# 5V0_12V0_rails.net
KiCad netlist of a schematic drawn in Altium Designer
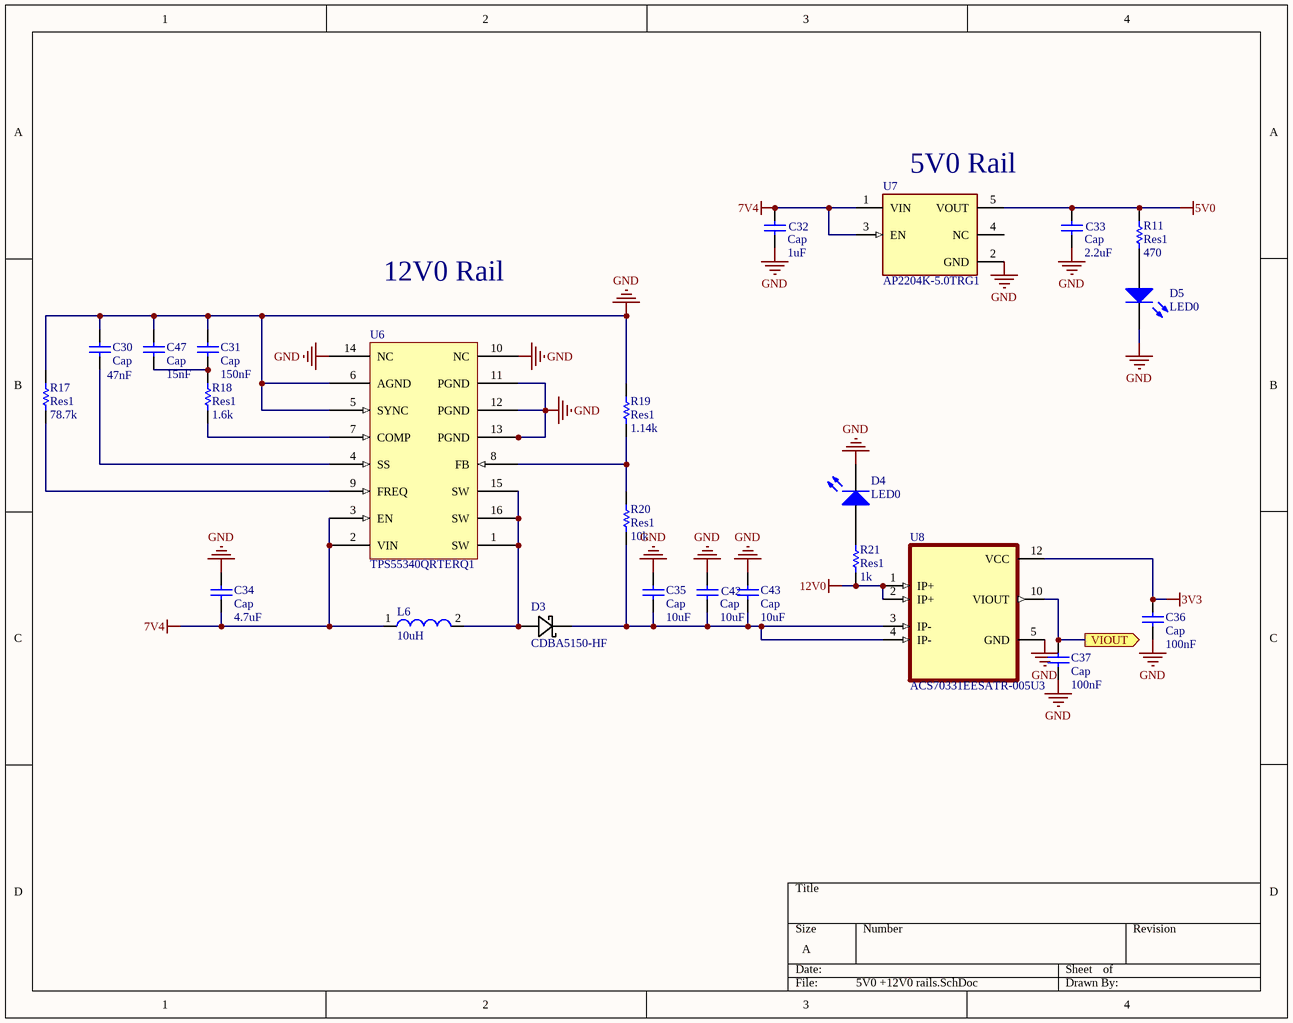
[diagram p0: 5V0 +12V0 rails.SchDoc]

(export (version "E")
  (design (tool "Eeschema 10.0.6"))
  (components
    (comp (ref "C30")
      (value "Cap")
      (footprint "0402-A")
      (description "Capacitor")
      (fields (field (name "ALTIUM_VALUE") "47nF") (field (name "PUBLISHER") "Altium Limited"))
      (libsource (lib "Miscellaneous Devices") (part "Cap"))
    )
    (comp (ref "C31")
      (value "Cap")
      (footprint "0402-A")
      (description "Capacitor")
      (fields (field (name "ALTIUM_VALUE") "150nF") (field (name "PUBLISHER") "Altium Limited"))
      (libsource (lib "Miscellaneous Devices") (part "Cap"))
    )
    (comp (ref "C32")
      (value "Cap")
      (footprint "1608[0603]")
      (description "Capacitor")
      (fields (field (name "ALTIUM_VALUE") "1uF") (field (name "PUBLISHER") "Altium Limited"))
      (libsource (lib "Miscellaneous Devices") (part "Cap"))
    )
    (comp (ref "C33")
      (value "Cap")
      (footprint "0402-A")
      (description "Capacitor")
      (fields (field (name "ALTIUM_VALUE") "2.2uF") (field (name "PUBLISHER") "Altium Limited"))
      (libsource (lib "Miscellaneous Devices") (part "Cap"))
    )
    (comp (ref "C34")
      (value "Cap")
      (footprint "6-0805_M")
      (description "Capacitor")
      (fields (field (name "ALTIUM_VALUE") "4.7uF") (field (name "PUBLISHER") "Altium Limited"))
      (libsource (lib "Miscellaneous Devices") (part "Cap"))
    )
    (comp (ref "C35")
      (value "Cap")
      (footprint "6-0805_M")
      (description "Capacitor")
      (fields (field (name "ALTIUM_VALUE") "10uF") (field (name "PUBLISHER") "Altium Limited"))
      (libsource (lib "Miscellaneous Devices") (part "Cap"))
    )
    (comp (ref "C36")
      (value "Cap")
      (footprint "1608[0603]")
      (description "Capacitor")
      (fields (field (name "ALTIUM_VALUE") "100nF") (field (name "PUBLISHER") "Altium Limited"))
      (libsource (lib "Miscellaneous Devices") (part "Cap"))
    )
    (comp (ref "C37")
      (value "Cap")
      (footprint "1608[0603]")
      (description "Capacitor")
      (fields (field (name "ALTIUM_VALUE") "100nF") (field (name "PUBLISHER") "Altium Limited"))
      (libsource (lib "Miscellaneous Devices") (part "Cap"))
    )
    (comp (ref "C42")
      (value "Cap")
      (footprint "6-0805_M")
      (description "Capacitor")
      (fields (field (name "ALTIUM_VALUE") "10uF") (field (name "PUBLISHER") "Altium Limited"))
      (libsource (lib "Miscellaneous Devices") (part "Cap"))
    )
    (comp (ref "C43")
      (value "Cap")
      (footprint "6-0805_M")
      (description "Capacitor")
      (fields (field (name "ALTIUM_VALUE") "10uF") (field (name "PUBLISHER") "Altium Limited"))
      (libsource (lib "Miscellaneous Devices") (part "Cap"))
    )
    (comp (ref "C47")
      (value "Cap")
      (footprint "0402-A")
      (description "Capacitor")
      (fields (field (name "ALTIUM_VALUE") "15nF") (field (name "PUBLISHER") "Altium Limited"))
      (libsource (lib "Miscellaneous Devices") (part "Cap"))
    )
    (comp (ref "D3")
      (value "CDBA5150-HF")
      (footprint "CDBA5")
      (description "No Description Available")
      (fields (field (name "COPYRIGHT") "Copyright (C) 2018 Accelerated Designs. All rights reserved"))
      (libsource (lib "schottlky diode 5A") (part "CDBA5150-HF"))
    )
    (comp (ref "D4")
      (value "LED0")
      (footprint "1608[0603]")
      (fields (field (name "PUBLISHER") "Altium Limited"))
      (libsource (lib "Miscellaneous Devices") (part "LED0"))
    )
    (comp (ref "D5")
      (value "LED0")
      (footprint "1608[0603]")
      (fields (field (name "PUBLISHER") "Altium Limited"))
      (libsource (lib "Miscellaneous Devices") (part "LED0"))
    )
    (comp (ref "L6")
      (value "10uH")
      (footprint "WE-PD-L")
      (description "SMD-Shielded Power Inductor WE-PD, L = 10.0 µH")
      (libsource (lib "Altium Content Vault") (part "PAS-IND-INDUCTOR-2"))
    )
    (comp (ref "R11")
      (value "Res1")
      (footprint "6-0805_M")
      (description "Resistor")
      (fields (field (name "ALTIUM_VALUE") "470") (field (name "PUBLISHER") "Altium Limited"))
      (libsource (lib "Miscellaneous Devices") (part "Res1"))
    )
    (comp (ref "R17")
      (value "Res1")
      (footprint "0402-A")
      (description "Resistor")
      (fields (field (name "ALTIUM_VALUE") "78.7k") (field (name "PUBLISHER") "Altium Limited"))
      (libsource (lib "Miscellaneous Devices") (part "Res1"))
    )
    (comp (ref "R18")
      (value "Res1")
      (footprint "0402-A")
      (description "Resistor")
      (fields (field (name "ALTIUM_VALUE") "1.6k") (field (name "PUBLISHER") "Altium Limited"))
      (libsource (lib "Miscellaneous Devices") (part "Res1"))
    )
    (comp (ref "R19")
      (value "Res1")
      (footprint "6-0805_M")
      (description "Resistor")
      (fields (field (name "ALTIUM_VALUE") "1.14k") (field (name "PUBLISHER") "Altium Limited"))
      (libsource (lib "Miscellaneous Devices") (part "Res1"))
    )
    (comp (ref "R20")
      (value "Res1")
      (footprint "0402-A")
      (description "Resistor")
      (fields (field (name "ALTIUM_VALUE") "10k") (field (name "PUBLISHER") "Altium Limited"))
      (libsource (lib "Miscellaneous Devices") (part "Res1"))
    )
    (comp (ref "R21")
      (value "Res1")
      (footprint "0402-A")
      (description "Resistor")
      (fields (field (name "ALTIUM_VALUE") "1k") (field (name "PUBLISHER") "Altium Limited"))
      (libsource (lib "Miscellaneous Devices") (part "Res1"))
    )
    (comp (ref "U6")
      (value "TPS55340QRTERQ1")
      (footprint "TPS55340QRTERQ1")
      (libsource (lib "TPS55340QRTERQ1") (part "TPS55340QRTERQ1"))
    )
    (comp (ref "U7")
      (value "AP2204K-5.0TRG1")
      (footprint "FP-SOT25-IPC_B")
      (description "IC REG LINEAR 5V 150MA SOT23-5")
      (libsource (lib "Altium Content Vault") (part "4edbc9a0bcf12f8a3abc99958da3ec2"))
    )
    (comp (ref "U8")
      (value "ACS70331EESATR-005U3")
      (footprint "ALLEGRO_ACS70331EESATR-005U3")
      (description "Current Sensor 5A 1 Channel Hall Effect, Open Loop Unidirectional 12-PowerWQFN")
      (fields
        (field (name "DIGI-KEY_PART_NUMBER") "620-1888-1-ND")
        (field (name "MF") "Allegro MicroSystems LLC")
      )
      (libsource (lib "ACS70331EESATR-005U3") (part "ACS70331EESATR-005U3"))
    )
  )
  (nets
    (net (code "1") (name "/VIOUT") (class "Default")
      (node (ref "C37") (pin "1") (pinfunction "1_1") (pintype "passive"))
      (node (ref "U8") (pin "10") (pinfunction "VIOUT_10") (pintype "output"))
    )
    (net (code "2") (name "3V3") (class "Default")
      (node (ref "C36") (pin "1") (pinfunction "1_1") (pintype "passive"))
      (node (ref "U8") (pin "12") (pinfunction "VCC_12") (pintype "power_in"))
    )
    (net (code "3") (name "5V0") (class "Default")
      (node (ref "C33") (pin "2") (pinfunction "2_2") (pintype "passive"))
      (node (ref "R11") (pin "2") (pinfunction "2_2") (pintype "passive"))
      (node (ref "U7") (pin "5") (pinfunction "VOUT_5") (pintype "power_in"))
    )
    (net (code "4") (name "7V4") (class "Default")
      (node (ref "C32") (pin "2") (pinfunction "2_2") (pintype "passive"))
      (node (ref "C34") (pin "1") (pinfunction "1_1") (pintype "passive"))
      (node (ref "L6") (pin "1") (pinfunction "1_1") (pintype "passive"))
      (node (ref "U6") (pin "2") (pinfunction "VIN_2") (pintype "power_in"))
      (node (ref "U6") (pin "3") (pinfunction "EN_3") (pintype "input"))
      (node (ref "U7") (pin "1") (pinfunction "VIN_1") (pintype "power_in"))
      (node (ref "U7") (pin "3") (pinfunction "EN_3") (pintype "input"))
    )
    (net (code "5") (name "12V0") (class "Default")
      (node (ref "R21") (pin "2") (pinfunction "2_2") (pintype "passive"))
      (node (ref "U8") (pin "1") (pinfunction "IP+_1") (pintype "input"))
      (node (ref "U8") (pin "2") (pinfunction "IP+_2") (pintype "input"))
    )
    (net (code "6") (name "GND") (class "Default")
      (node (ref "C30") (pin "2") (pinfunction "2_2") (pintype "passive"))
      (node (ref "C31") (pin "2") (pinfunction "2_2") (pintype "passive"))
      (node (ref "C32") (pin "1") (pinfunction "1_1") (pintype "passive"))
      (node (ref "C33") (pin "1") (pinfunction "1_1") (pintype "passive"))
      (node (ref "C34") (pin "2") (pinfunction "2_2") (pintype "passive"))
      (node (ref "C35") (pin "2") (pinfunction "2_2") (pintype "passive"))
      (node (ref "C36") (pin "2") (pinfunction "2_2") (pintype "passive"))
      (node (ref "C37") (pin "2") (pinfunction "2_2") (pintype "passive"))
      (node (ref "C42") (pin "2") (pinfunction "2_2") (pintype "passive"))
      (node (ref "C43") (pin "2") (pinfunction "2_2") (pintype "passive"))
      (node (ref "C47") (pin "2") (pinfunction "2_2") (pintype "passive"))
      (node (ref "D4") (pin "2") (pinfunction "K_2") (pintype "passive"))
      (node (ref "D5") (pin "2") (pinfunction "K_2") (pintype "passive"))
      (node (ref "R17") (pin "2") (pinfunction "2_2") (pintype "passive"))
      (node (ref "R19") (pin "2") (pinfunction "2_2") (pintype "passive"))
      (node (ref "U6") (pin "10") (pinfunction "NC_10") (pintype "passive"))
      (node (ref "U6") (pin "11") (pinfunction "PGND_11") (pintype "power_in"))
      (node (ref "U6") (pin "12") (pinfunction "PGND_12") (pintype "power_in"))
      (node (ref "U6") (pin "13") (pinfunction "PGND_13") (pintype "power_in"))
      (node (ref "U6") (pin "14") (pinfunction "NC_14") (pintype "passive"))
      (node (ref "U6") (pin "17") (pinfunction "17_17") (pintype "power_in"))
      (node (ref "U6") (pin "5") (pinfunction "SYNC_5") (pintype "input"))
      (node (ref "U6") (pin "6") (pinfunction "AGND_6") (pintype "power_in"))
      (node (ref "U7") (pin "2") (pinfunction "GND_2") (pintype "power_in"))
      (node (ref "U8") (pin "5") (pinfunction "GND_5") (pintype "power_in"))
    )
    (net (code "7") (name "Net-(C31-Pad1)") (class "Default")
      (node (ref "C31") (pin "1") (pinfunction "1_1") (pintype "passive"))
      (node (ref "C47") (pin "1") (pinfunction "1_1") (pintype "passive"))
      (node (ref "R18") (pin "2") (pinfunction "2_2") (pintype "passive"))
    )
    (net (code "8") (name "Net-(C35-Pad1)") (class "Default")
      (node (ref "C35") (pin "1") (pinfunction "1_1") (pintype "passive"))
      (node (ref "C42") (pin "1") (pinfunction "1_1") (pintype "passive"))
      (node (ref "C43") (pin "1") (pinfunction "1_1") (pintype "passive"))
      (node (ref "D3") (pin "1") (pinfunction "1_1") (pintype "passive"))
      (node (ref "R20") (pin "1") (pinfunction "1_1") (pintype "passive"))
      (node (ref "U8") (pin "3") (pinfunction "IP-_3") (pintype "input"))
      (node (ref "U8") (pin "4") (pinfunction "IP-_4") (pintype "input"))
    )
    (net (code "9") (name "Net-(D3-Pad2)") (class "Default")
      (node (ref "D3") (pin "2") (pinfunction "2_2") (pintype "passive"))
      (node (ref "L6") (pin "2") (pinfunction "2_2") (pintype "passive"))
      (node (ref "U6") (pin "1") (pinfunction "SW_1") (pintype "power_in"))
      (node (ref "U6") (pin "15") (pinfunction "SW_15") (pintype "power_in"))
      (node (ref "U6") (pin "16") (pinfunction "SW_16") (pintype "power_in"))
    )
    (net (code "10") (name "Net-(D4-A)") (class "Default")
      (node (ref "D4") (pin "1") (pinfunction "A_1") (pintype "passive"))
      (node (ref "R21") (pin "1") (pinfunction "1_1") (pintype "passive"))
    )
    (net (code "11") (name "Net-(D5-A)") (class "Default")
      (node (ref "D5") (pin "1") (pinfunction "A_1") (pintype "passive"))
      (node (ref "R11") (pin "1") (pinfunction "1_1") (pintype "passive"))
    )
    (net (code "12") (name "Net-(U6-COMP)") (class "Default")
      (node (ref "R18") (pin "1") (pinfunction "1_1") (pintype "passive"))
      (node (ref "U6") (pin "7") (pinfunction "COMP_7") (pintype "input"))
    )
    (net (code "13") (name "Net-(U6-FB)") (class "Default")
      (node (ref "R19") (pin "1") (pinfunction "1_1") (pintype "passive"))
      (node (ref "R20") (pin "2") (pinfunction "2_2") (pintype "passive"))
      (node (ref "U6") (pin "8") (pinfunction "FB_8") (pintype "input"))
    )
    (net (code "14") (name "Net-(U6-FREQ)") (class "Default")
      (node (ref "R17") (pin "1") (pinfunction "1_1") (pintype "passive"))
      (node (ref "U6") (pin "9") (pinfunction "FREQ_9") (pintype "input"))
    )
    (net (code "15") (name "Net-(U6-SS)") (class "Default")
      (node (ref "C30") (pin "1") (pinfunction "1_1") (pintype "passive"))
      (node (ref "U6") (pin "4") (pinfunction "SS_4") (pintype "input"))
    )
    (net (code "16") (name "unconnected-(U7-NC-Pad4)") (class "Default")
      (node (ref "U7") (pin "4") (pinfunction "NC_4") (pintype "passive"))
    )
  )
)
